# tof.net
KiCad netlist of a schematic drawn in Altium Designer
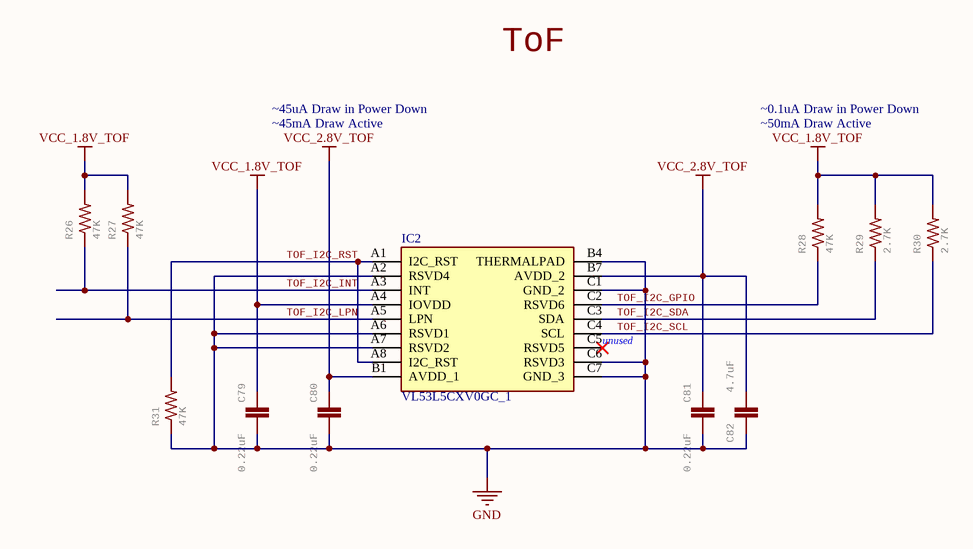
[diagram p0: tof.SchDoc]

(export (version "E")
  (design (tool "Eeschema 10.0.6"))
  (components
    (comp (ref "C79")
      (value "0.22uF")
      (footprint "C0201")
      (description "CAPACITOR, European symbol")
      (fields (field (name "MPN") "GRM033R60J224ME15D"))
      (libsource (lib "openmv-ae3") (part "C-EUC0201"))
    )
    (comp (ref "C80")
      (value "0.22uF")
      (footprint "C0201")
      (description "CAPACITOR, European symbol")
      (fields (field (name "MPN") "GRM033R60J224ME15D"))
      (libsource (lib "openmv-ae3") (part "C-EUC0201"))
    )
    (comp (ref "C81")
      (value "0.22uF")
      (footprint "C0201")
      (description "CAPACITOR, European symbol")
      (fields (field (name "MPN") "GRM033R60J224ME15D"))
      (libsource (lib "openmv-ae3") (part "C-EUC0201"))
    )
    (comp (ref "C82")
      (value "4.7uF")
      (footprint "0402-CAP")
      (description "0402 (1005 Metric) Nick Garner - TeleSense")
      (fields (field (name "MPN") "JMK105BBJ475MV-F"))
      (libsource (lib "openmv-ae3") (part "CAP_0402"))
    )
    (comp (ref "IC2")
      (value "VL53L5CXV0GC_1")
      (footprint "SamacSys:VL53L5CXV0GC1")
      (description "Integrated Circuit")
      (fields
        (field (name "MANUFACTURER_PART_NUMBER") "VL53L5CXV0GC/1")
        (field (name "MOUSER PART NUMBER") "511-VL53L5CXV0GC/1")
      )
      (libsource (lib "openmv-ae3") (part "VL53L5CXV0GC_1"))
    )
    (comp (ref "R26")
      (value "47K")
      (footprint "R0201")
      (fields (field (name "MPN") "RMCF0201FT47K0") (field (name "LIBRARYNAME") "sfe"))
      (libsource (lib "openmv-ae3") (part "RESISTOR0402-RES"))
    )
    (comp (ref "R27")
      (value "47K")
      (footprint "R0201")
      (fields (field (name "MPN") "RMCF0201FT47K0") (field (name "LIBRARYNAME") "sfe"))
      (libsource (lib "openmv-ae3") (part "RESISTOR0402-RES"))
    )
    (comp (ref "R28")
      (value "47K")
      (footprint "R0201")
      (fields (field (name "MPN") "RMCF0201FT47K0") (field (name "LIBRARYNAME") "sfe"))
      (libsource (lib "openmv-ae3") (part "RESISTOR0402-RES"))
    )
    (comp (ref "R29")
      (value "2.7K")
      (footprint "R0201")
      (fields (field (name "MPN") "RC0201JR-072K7L") (field (name "LIBRARYNAME") "sfe"))
      (libsource (lib "openmv-ae3") (part "RESISTOR0402-RES"))
    )
    (comp (ref "R30")
      (value "2.7K")
      (footprint "R0201")
      (fields (field (name "MPN") "RC0201JR-072K7L") (field (name "LIBRARYNAME") "sfe"))
      (libsource (lib "openmv-ae3") (part "RESISTOR0402-RES"))
    )
    (comp (ref "R31")
      (value "47K")
      (footprint "R0201")
      (fields (field (name "MPN") "RMCF0201FT47K0") (field (name "LIBRARYNAME") "sfe"))
      (libsource (lib "openmv-ae3") (part "RESISTOR0402-RES"))
    )
  )
  (nets
    (net (code "1") (name "/TOF_I2C_GPIO") (class "Default")
      (node (ref "IC2") (pin "C2") (pinfunction "RSVD6_C2") (pintype "passive"))
      (node (ref "R28") (pin "1") (pinfunction "1_1") (pintype "passive"))
    )
    (net (code "2") (name "/TOF_I2C_INT") (class "Default")
      (node (ref "IC2") (pin "A3") (pinfunction "INT_A3") (pintype "passive"))
      (node (ref "R26") (pin "1") (pinfunction "1_1") (pintype "passive"))
    )
    (net (code "3") (name "/TOF_I2C_LPN") (class "Default")
      (node (ref "IC2") (pin "A5") (pinfunction "LPN_A5") (pintype "passive"))
      (node (ref "R27") (pin "1") (pinfunction "1_1") (pintype "passive"))
    )
    (net (code "4") (name "/TOF_I2C_RST") (class "Default")
      (node (ref "IC2") (pin "A1") (pinfunction "I2C_RST_A1") (pintype "passive"))
      (node (ref "IC2") (pin "A8") (pinfunction "I2C_RST_A8") (pintype "passive"))
      (node (ref "R31") (pin "2") (pinfunction "2_2") (pintype "passive"))
    )
    (net (code "5") (name "/TOF_I2C_SCL") (class "Default")
      (node (ref "IC2") (pin "C4") (pinfunction "SCL_C4") (pintype "passive"))
      (node (ref "R30") (pin "1") (pinfunction "1_1") (pintype "passive"))
    )
    (net (code "6") (name "/TOF_I2C_SDA") (class "Default")
      (node (ref "IC2") (pin "C3") (pinfunction "SDA_C3") (pintype "passive"))
      (node (ref "R29") (pin "1") (pinfunction "1_1") (pintype "passive"))
    )
    (net (code "7") (name "GND") (class "Default")
      (node (ref "C79") (pin "2") (pinfunction "2_2") (pintype "passive"))
      (node (ref "C80") (pin "2") (pinfunction "2_2") (pintype "passive"))
      (node (ref "C81") (pin "2") (pinfunction "2_2") (pintype "passive"))
      (node (ref "C82") (pin "1") (pinfunction "1_1") (pintype "passive"))
      (node (ref "IC2") (pin "A2") (pinfunction "RSVD4_A2") (pintype "passive"))
      (node (ref "IC2") (pin "A6") (pinfunction "RSVD1_A6") (pintype "passive"))
      (node (ref "IC2") (pin "A7") (pinfunction "RSVD2_A7") (pintype "passive"))
      (node (ref "IC2") (pin "B4") (pinfunction "THERMALPAD_B4") (pintype "passive"))
      (node (ref "IC2") (pin "C1") (pinfunction "GND_2_C1") (pintype "passive"))
      (node (ref "IC2") (pin "C6") (pinfunction "RSVD3_C6") (pintype "passive"))
      (node (ref "IC2") (pin "C7") (pinfunction "GND_3_C7") (pintype "passive"))
      (node (ref "R31") (pin "1") (pinfunction "1_1") (pintype "passive"))
    )
    (net (code "8") (name "VCC_1.8V_TOF") (class "Default")
      (node (ref "C79") (pin "1") (pinfunction "1_1") (pintype "passive"))
      (node (ref "IC2") (pin "A4") (pinfunction "IOVDD_A4") (pintype "passive"))
      (node (ref "R26") (pin "2") (pinfunction "2_2") (pintype "passive"))
      (node (ref "R27") (pin "2") (pinfunction "2_2") (pintype "passive"))
      (node (ref "R28") (pin "2") (pinfunction "2_2") (pintype "passive"))
      (node (ref "R29") (pin "2") (pinfunction "2_2") (pintype "passive"))
      (node (ref "R30") (pin "2") (pinfunction "2_2") (pintype "passive"))
    )
    (net (code "9") (name "VCC_2.8V_TOF") (class "Default")
      (node (ref "C80") (pin "1") (pinfunction "1_1") (pintype "passive"))
      (node (ref "C81") (pin "1") (pinfunction "1_1") (pintype "passive"))
      (node (ref "C82") (pin "2") (pinfunction "2_2") (pintype "passive"))
      (node (ref "IC2") (pin "B1") (pinfunction "AVDD_1_B1") (pintype "passive"))
      (node (ref "IC2") (pin "B7") (pinfunction "AVDD_2_B7") (pintype "passive"))
    )
    (net (code "10") (name "unconnected-(IC2-RSVD5-PadC5)") (class "Default")
      (node (ref "IC2") (pin "C5") (pinfunction "RSVD5_C5") (pintype "passive+no_connect"))
    )
  )
)
